# LC_LPF4.net
KiCad netlist of a schematic drawn in Altium Designer
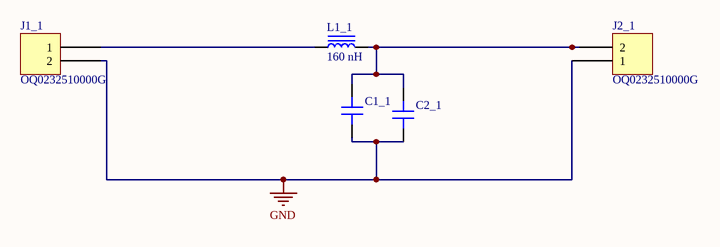
[diagram p0: LC_LPF4.SchDoc]

(export (version "E")
  (design (tool "Eeschema 10.0.6"))
  (components
    (comp (ref "C1_1")
      (value "~")
      (footprint "CAP 0603_1608")
      (description "CAP CER 10PF 100V C0G/NPO 0603")
      (fields (field (name "PART NUMBER") "AC0603JRNPO0BN100") (field (name "MANUFACTURER") "Yageo"))
      (libsource (lib "Celestial Altium Library - altium_library") (part "Capacitor"))
    )
    (comp (ref "C2_1")
      (value "~")
      (footprint "CAP 0603_1608")
      (description "CAP CER 10PF 100V C0G/NPO 0603")
      (fields (field (name "PART NUMBER") "AC0603JRNPO0BN100") (field (name "MANUFACTURER") "Yageo"))
      (libsource (lib "Celestial Altium Library - altium_library") (part "Capacitor"))
    )
    (comp (ref "J1_1")
      (value "OQ0232510000G")
      (footprint "FCI 06-381-2PIN")
      (description "TERM BLOCK HDR 2POS 90DEG 3.81MM")
      (fields (field (name "MANUFACTURER") "Amphenol Anytek"))
      (libsource (lib "") (part "2 Pin_1"))
    )
    (comp (ref "J2_1")
      (value "OQ0232510000G")
      (footprint "FCI 06-381-2PIN")
      (description "TERM BLOCK HDR 2POS 90DEG 3.81MM")
      (fields (field (name "MANUFACTURER") "Amphenol Anytek"))
      (libsource (lib "Celestial Altium Library - altium_library") (part "2 Pin"))
    )
    (comp (ref "L1_1")
      (value "160 nH")
      (footprint "IND 0402_1005 RF WW")
      (description "FIXED IND 160NH 480MA 330MOHM SM")
      (fields
        (field (name "PART NUMBER") "LQW15CNR16J00D")
        (field (name "MANUFACTURER") "Murata Electronics")
      )
      (libsource (lib "Celestial Altium Library - altium_library") (part "Inductor"))
    )
  )
  (nets
    (net (code "1") (name "GND") (class "Default")
      (node (ref "C1_1") (pin "1") (pinfunction "1_1") (pintype "passive"))
      (node (ref "C2_1") (pin "1") (pinfunction "1_1") (pintype "passive"))
      (node (ref "J1_1") (pin "2") (pinfunction "2_2") (pintype "passive"))
      (node (ref "J2_1") (pin "1") (pinfunction "1_1") (pintype "passive"))
    )
    (net (code "2") (name "Net-(C1_1-Pad2)") (class "Default")
      (node (ref "C1_1") (pin "2") (pinfunction "2_2") (pintype "passive"))
      (node (ref "C2_1") (pin "2") (pinfunction "2_2") (pintype "passive"))
      (node (ref "J2_1") (pin "2") (pinfunction "2_2") (pintype "passive"))
      (node (ref "L1_1") (pin "2") (pinfunction "2_2") (pintype "passive"))
    )
    (net (code "3") (name "Net-(J1_1-Pad1)") (class "Default")
      (node (ref "J1_1") (pin "1") (pinfunction "1_1") (pintype "passive"))
      (node (ref "L1_1") (pin "1") (pinfunction "1_1") (pintype "passive"))
    )
  )
)
